# Adafruit_OLED_128x32_Mono_I2C_STEMMA_QT_.net
KiCad netlist of a schematic drawn in EAGLE
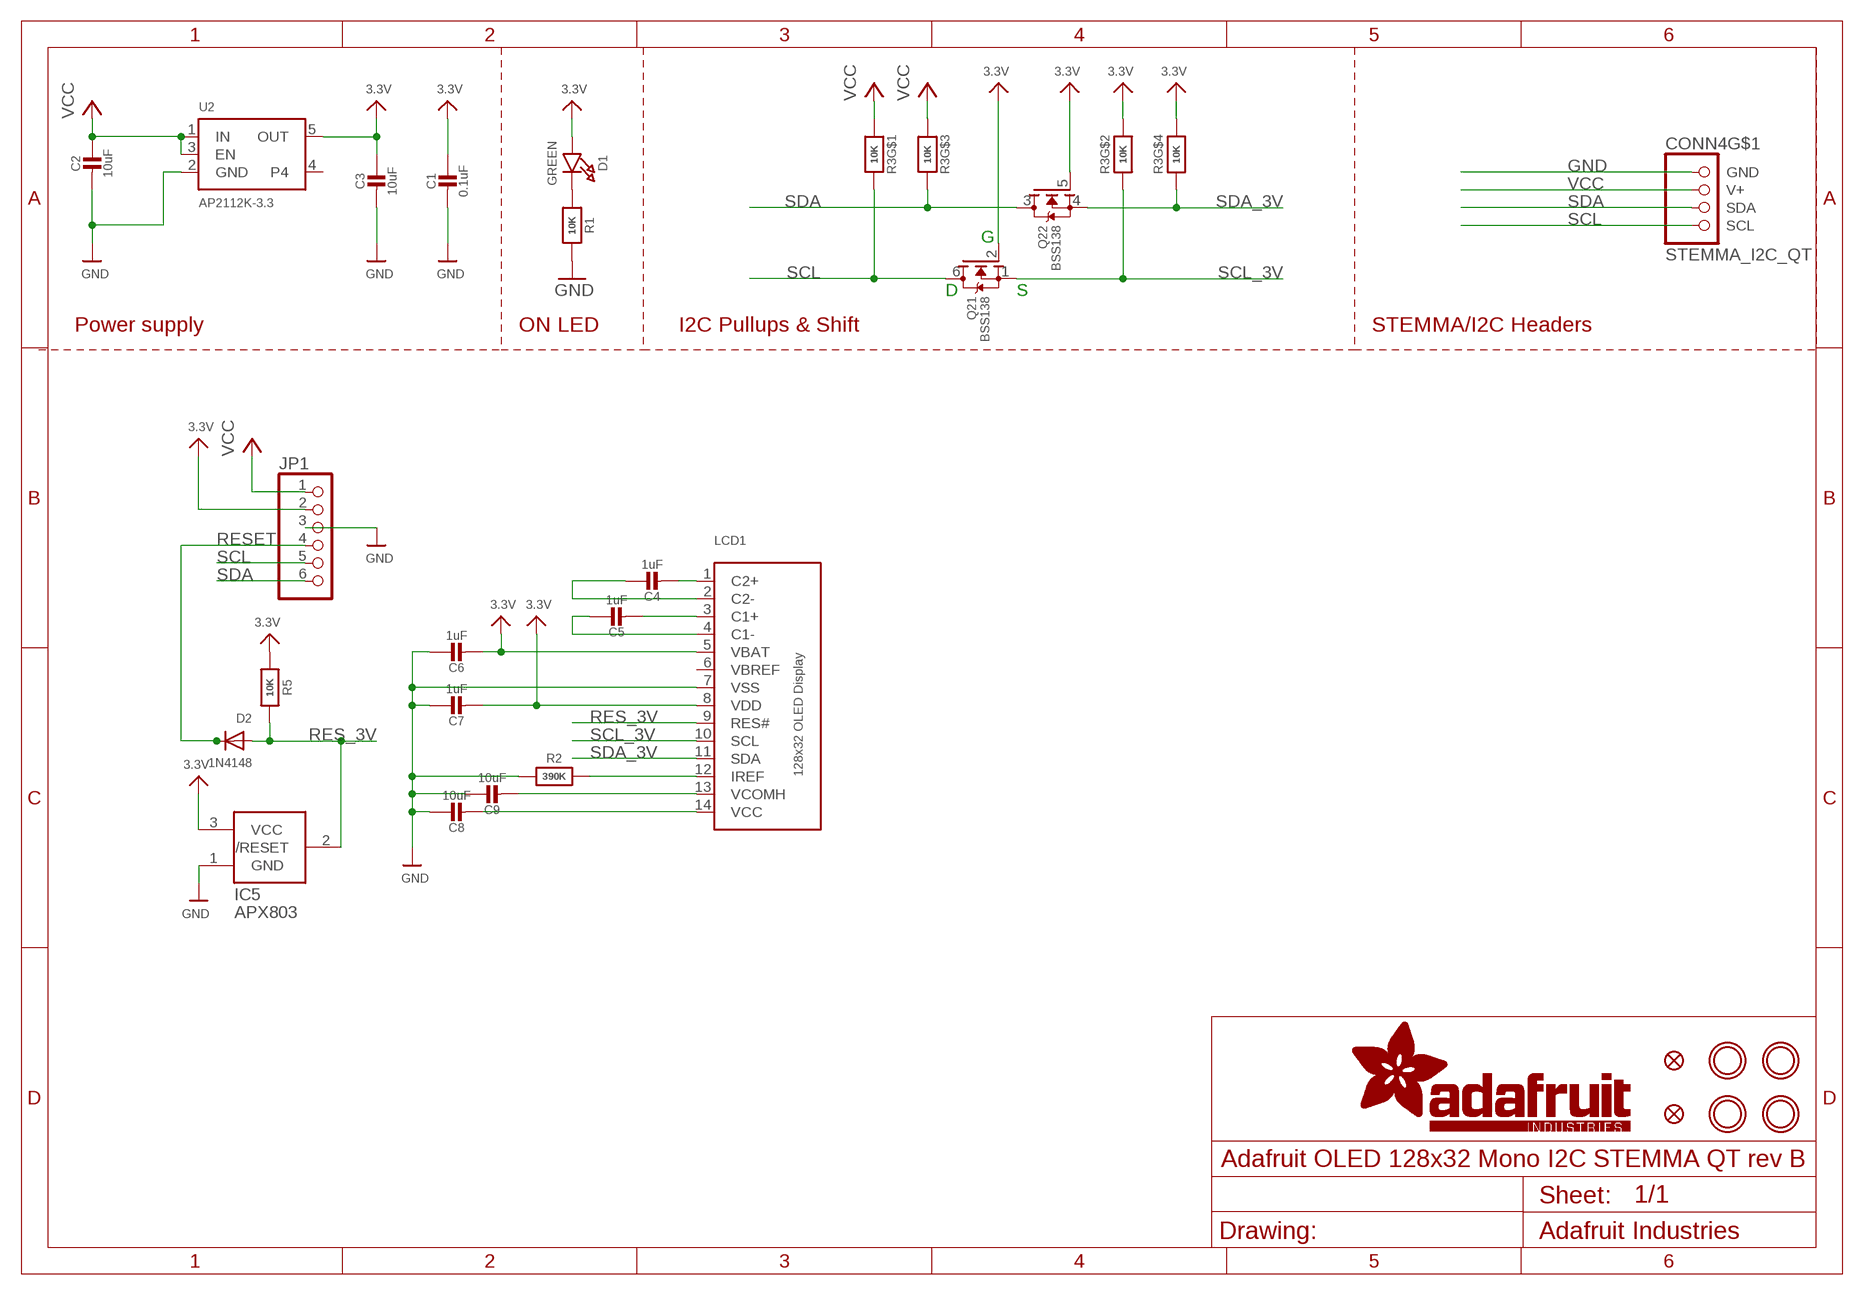
[diagram p0: schematic, sheet 1]

(export (version "E")
  (design (tool "Eeschema 10.0.6"))
  (components
    (comp (ref "C1")
      (value "0.1uF")
      (footprint "eagle-import:0603-NO")
      (libsource (lib "eagle-import") (part "CAP_CERAMIC0603_NO"))
    )
    (comp (ref "C2")
      (value "10uF")
      (footprint "eagle-import:0805-NO")
      (libsource (lib "eagle-import") (part "CAP_CERAMIC0805-NOOUTLINE"))
    )
    (comp (ref "C3")
      (value "10uF")
      (footprint "eagle-import:0805-NO")
      (libsource (lib "eagle-import") (part "CAP_CERAMIC0805-NOOUTLINE"))
    )
    (comp (ref "C4")
      (value "1uF")
      (footprint "eagle-import:0805-NO")
      (libsource (lib "eagle-import") (part "CAP_CERAMIC0805-NOOUTLINE"))
    )
    (comp (ref "C5")
      (value "1uF")
      (footprint "eagle-import:0805-NO")
      (libsource (lib "eagle-import") (part "CAP_CERAMIC0805-NOOUTLINE"))
    )
    (comp (ref "C6")
      (value "1uF")
      (footprint "eagle-import:0805-NO")
      (libsource (lib "eagle-import") (part "CAP_CERAMIC0805-NOOUTLINE"))
    )
    (comp (ref "C7")
      (value "1uF")
      (footprint "eagle-import:0805-NO")
      (libsource (lib "eagle-import") (part "CAP_CERAMIC0805-NOOUTLINE"))
    )
    (comp (ref "C8")
      (value "10uF")
      (footprint "eagle-import:0805-NO")
      (libsource (lib "eagle-import") (part "CAP_CERAMIC0805-NOOUTLINE"))
    )
    (comp (ref "C9")
      (value "10uF")
      (footprint "eagle-import:0805-NO")
      (libsource (lib "eagle-import") (part "CAP_CERAMIC0805-NOOUTLINE"))
    )
    (comp (ref "CONN4")
      (value "STEMMA_I2C_QT")
      (footprint "eagle-import:JST_SH4")
      (libsource (lib "eagle-import") (part "STEMMA_I2C_QT"))
    )
    (comp (ref "D1")
      (value "GREEN")
      (footprint "eagle-import:CHIPLED_0603_NOOUTLINE")
      (libsource (lib "eagle-import") (part "LED0603_NOOUTLINE"))
    )
    (comp (ref "D2")
      (value "1N4148")
      (footprint "eagle-import:SOD-323F")
      (libsource (lib "eagle-import") (part "DIODESOD-323F"))
    )
    (comp (ref "FID3")
      (value "FIDUCIAL_1MM")
      (footprint "eagle-import:FIDUCIAL_1MM")
      (libsource (lib "eagle-import") (part "FIDUCIAL_1MM"))
    )
    (comp (ref "FID4")
      (value "FIDUCIAL_1MM")
      (footprint "eagle-import:FIDUCIAL_1MM")
      (libsource (lib "eagle-import") (part "FIDUCIAL_1MM"))
    )
    (comp (ref "IC5")
      (value "APX803")
      (footprint "eagle-import:SOT23")
      (libsource (lib "eagle-import") (part "AXP083-SAG"))
    )
    (comp (ref "JP1")
      (value "HEADER-1X670MIL")
      (footprint "eagle-import:1X06_ROUND_70")
      (libsource (lib "eagle-import") (part "HEADER-1X670MIL"))
    )
    (comp (ref "LCD1")
      (value "DISP_OLED_UG-2832HSWEG02")
      (footprint "eagle-import:UG-2832HSWEG02_WRAPUNDER")
      (libsource (lib "eagle-import") (part "DISP_OLED_UG-2832HSWEG02"))
    )
    (comp (ref "Q2")
      (value "BSS138")
      (footprint "eagle-import:SOT363")
      (libsource (lib "eagle-import") (part "MOSFET-N_DUAL"))
    )
    (comp (ref "R1")
      (value "10K")
      (footprint "eagle-import:0603-NO")
      (libsource (lib "eagle-import") (part "RESISTOR_0603_NOOUT"))
    )
    (comp (ref "R2")
      (value "390K")
      (footprint "eagle-import:0603-NO")
      (libsource (lib "eagle-import") (part "RESISTOR_0603_NOOUT"))
    )
    (comp (ref "R3")
      (value "10K")
      (footprint "eagle-import:RESPACK_4X0603")
      (libsource (lib "eagle-import") (part "RESISTOR_4PACK"))
    )
    (comp (ref "R5")
      (value "10K")
      (footprint "eagle-import:0603-NO")
      (libsource (lib "eagle-import") (part "RESISTOR_0603_NOOUT"))
    )
    (comp (ref "U$1")
      (value "MOUNTINGHOLE2.5")
      (footprint "eagle-import:MOUNTINGHOLE_2.5_PLATED")
      (libsource (lib "eagle-import") (part "MOUNTINGHOLE2.5"))
    )
    (comp (ref "U$17")
      (value "MOUNTINGHOLE2.5")
      (footprint "eagle-import:MOUNTINGHOLE_2.5_PLATED")
      (libsource (lib "eagle-import") (part "MOUNTINGHOLE2.5"))
    )
    (comp (ref "U$19")
      (value "MOUNTINGHOLE2.5")
      (footprint "eagle-import:MOUNTINGHOLE_2.5_PLATED")
      (libsource (lib "eagle-import") (part "MOUNTINGHOLE2.5"))
    )
    (comp (ref "U$21")
      (value "MOUNTINGHOLE2.5")
      (footprint "eagle-import:MOUNTINGHOLE_2.5_PLATED")
      (libsource (lib "eagle-import") (part "MOUNTINGHOLE2.5"))
    )
    (comp (ref "U2")
      (value "AP2112K-3.3")
      (footprint "eagle-import:SOT23-5")
      (libsource (lib "eagle-import") (part "VREG_SOT23-5"))
    )
  )
  (nets
    (net (code "1") (name "/RESET") (class "Default")
      (node (ref "D2") (pin "C") (pinfunction "C_C") (pintype "passive"))
      (node (ref "JP1") (pin "4") (pinfunction "4_4") (pintype "passive"))
    )
    (net (code "2") (name "/RES_3V") (class "Default")
      (node (ref "D2") (pin "A") (pinfunction "A_A") (pintype "passive"))
      (node (ref "IC5") (pin "2") (pinfunction "/RESET_2") (pintype "output"))
      (node (ref "LCD1") (pin "9") (pinfunction "RES#_9") (pintype "bidirectional"))
      (node (ref "R5") (pin "1") (pinfunction "1_1") (pintype "passive"))
    )
    (net (code "3") (name "/SCL") (class "Default")
      (node (ref "CONN4") (pin "4") (pinfunction "SCL_4") (pintype "passive"))
      (node (ref "JP1") (pin "5") (pinfunction "5_5") (pintype "passive"))
      (node (ref "Q2") (pin "6") (pinfunction "D_6") (pintype "bidirectional"))
      (node (ref "R3") (pin "8") (pinfunction "2_8") (pintype "passive"))
    )
    (net (code "4") (name "/SCL_3V") (class "Default")
      (node (ref "LCD1") (pin "10") (pinfunction "SCL_10") (pintype "bidirectional"))
      (node (ref "Q2") (pin "1") (pinfunction "S_1") (pintype "bidirectional"))
      (node (ref "R3") (pin "7") (pinfunction "2_7") (pintype "passive"))
    )
    (net (code "5") (name "/SDA") (class "Default")
      (node (ref "CONN4") (pin "3") (pinfunction "SDA_3") (pintype "passive"))
      (node (ref "JP1") (pin "6") (pinfunction "6_6") (pintype "passive"))
      (node (ref "Q2") (pin "3") (pinfunction "D_3") (pintype "bidirectional"))
      (node (ref "R3") (pin "6") (pinfunction "2_6") (pintype "passive"))
    )
    (net (code "6") (name "/SDA_3V") (class "Default")
      (node (ref "LCD1") (pin "11") (pinfunction "SDA_11") (pintype "bidirectional"))
      (node (ref "Q2") (pin "4") (pinfunction "S_4") (pintype "bidirectional"))
      (node (ref "R3") (pin "5") (pinfunction "2_5") (pintype "passive"))
    )
    (net (code "7") (name "/VBREF") (class "Default")
      (node (ref "LCD1") (pin "6") (pinfunction "VBREF_6") (pintype "power_in"))
    )
    (net (code "8") (name "3.3V") (class "Default")
      (node (ref "C1") (pin "1") (pinfunction "1_1") (pintype "passive"))
      (node (ref "C3") (pin "1") (pinfunction "1_1") (pintype "passive"))
      (node (ref "C6") (pin "2") (pinfunction "2_2") (pintype "passive"))
      (node (ref "C7") (pin "2") (pinfunction "2_2") (pintype "passive"))
      (node (ref "D1") (pin "A") (pinfunction "A_A") (pintype "passive"))
      (node (ref "IC5") (pin "3") (pinfunction "VCC_3") (pintype "power_in"))
      (node (ref "JP1") (pin "2") (pinfunction "2_2") (pintype "passive"))
      (node (ref "LCD1") (pin "5") (pinfunction "VBAT_5") (pintype "power_in"))
      (node (ref "LCD1") (pin "8") (pinfunction "VDD_8") (pintype "power_in"))
      (node (ref "Q2") (pin "2") (pinfunction "G_2") (pintype "bidirectional"))
      (node (ref "Q2") (pin "5") (pinfunction "G_5") (pintype "bidirectional"))
      (node (ref "R3") (pin "2") (pinfunction "1_2") (pintype "passive"))
      (node (ref "R3") (pin "4") (pinfunction "1_4") (pintype "passive"))
      (node (ref "R5") (pin "2") (pinfunction "2_2") (pintype "passive"))
      (node (ref "U2") (pin "5") (pinfunction "OUT_5") (pintype "power_in"))
    )
    (net (code "9") (name "GND") (class "Default")
      (node (ref "C1") (pin "2") (pinfunction "2_2") (pintype "passive"))
      (node (ref "C2") (pin "2") (pinfunction "2_2") (pintype "passive"))
      (node (ref "C3") (pin "2") (pinfunction "2_2") (pintype "passive"))
      (node (ref "C6") (pin "1") (pinfunction "1_1") (pintype "passive"))
      (node (ref "C7") (pin "1") (pinfunction "1_1") (pintype "passive"))
      (node (ref "C8") (pin "1") (pinfunction "1_1") (pintype "passive"))
      (node (ref "C9") (pin "1") (pinfunction "1_1") (pintype "passive"))
      (node (ref "CONN4") (pin "1") (pinfunction "GND_1") (pintype "passive"))
      (node (ref "IC5") (pin "1") (pinfunction "GND_1") (pintype "power_in"))
      (node (ref "JP1") (pin "3") (pinfunction "3_3") (pintype "passive"))
      (node (ref "LCD1") (pin "7") (pinfunction "VSS_7") (pintype "power_in"))
      (node (ref "R1") (pin "2") (pinfunction "2_2") (pintype "passive"))
      (node (ref "R2") (pin "1") (pinfunction "1_1") (pintype "passive"))
      (node (ref "U2") (pin "2") (pinfunction "GND_2") (pintype "power_in"))
    )
    (net (code "10") (name "Net-(D1-PadC)") (class "Default")
      (node (ref "D1") (pin "C") (pinfunction "C_C") (pintype "passive"))
      (node (ref "R1") (pin "1") (pinfunction "1_1") (pintype "passive"))
    )
    (net (code "11") (name "Net-(LCD1-C1+)") (class "Default")
      (node (ref "C5") (pin "2") (pinfunction "2_2") (pintype "passive"))
      (node (ref "LCD1") (pin "3") (pinfunction "C1+_3") (pintype "bidirectional"))
    )
    (net (code "12") (name "Net-(LCD1-C1-)") (class "Default")
      (node (ref "C5") (pin "1") (pinfunction "1_1") (pintype "passive"))
      (node (ref "LCD1") (pin "4") (pinfunction "C1-_4") (pintype "bidirectional"))
    )
    (net (code "13") (name "Net-(LCD1-C2+)") (class "Default")
      (node (ref "C4") (pin "2") (pinfunction "2_2") (pintype "passive"))
      (node (ref "LCD1") (pin "1") (pinfunction "C2+_1") (pintype "bidirectional"))
    )
    (net (code "14") (name "Net-(LCD1-C2-)") (class "Default")
      (node (ref "C4") (pin "1") (pinfunction "1_1") (pintype "passive"))
      (node (ref "LCD1") (pin "2") (pinfunction "C2-_2") (pintype "bidirectional"))
    )
    (net (code "15") (name "Net-(LCD1-IREF)") (class "Default")
      (node (ref "LCD1") (pin "12") (pinfunction "IREF_12") (pintype "bidirectional"))
      (node (ref "R2") (pin "2") (pinfunction "2_2") (pintype "passive"))
    )
    (net (code "16") (name "Net-(LCD1-VCC)") (class "Default")
      (node (ref "C8") (pin "2") (pinfunction "2_2") (pintype "passive"))
      (node (ref "LCD1") (pin "14") (pinfunction "VCC_14") (pintype "power_in"))
    )
    (net (code "17") (name "Net-(LCD1-VCOMH)") (class "Default")
      (node (ref "C9") (pin "2") (pinfunction "2_2") (pintype "passive"))
      (node (ref "LCD1") (pin "13") (pinfunction "VCOMH_13") (pintype "power_in"))
    )
    (net (code "18") (name "VCC") (class "Default")
      (node (ref "C2") (pin "1") (pinfunction "1_1") (pintype "passive"))
      (node (ref "CONN4") (pin "2") (pinfunction "V+_2") (pintype "passive"))
      (node (ref "JP1") (pin "1") (pinfunction "1_1") (pintype "passive"))
      (node (ref "R3") (pin "1") (pinfunction "1_1") (pintype "passive"))
      (node (ref "R3") (pin "3") (pinfunction "1_3") (pintype "passive"))
      (node (ref "U2") (pin "1") (pinfunction "IN_1") (pintype "power_in"))
      (node (ref "U2") (pin "3") (pinfunction "EN_3") (pintype "input"))
    )
    (net (code "19") (name "unconnected-(U2-P4-Pad4)") (class "Default")
      (node (ref "U2") (pin "4") (pinfunction "P4_4") (pintype "bidirectional"))
    )
  )
)
